# Pink-Noise-Filter.net
KiCad netlist of a schematic drawn in EAGLE
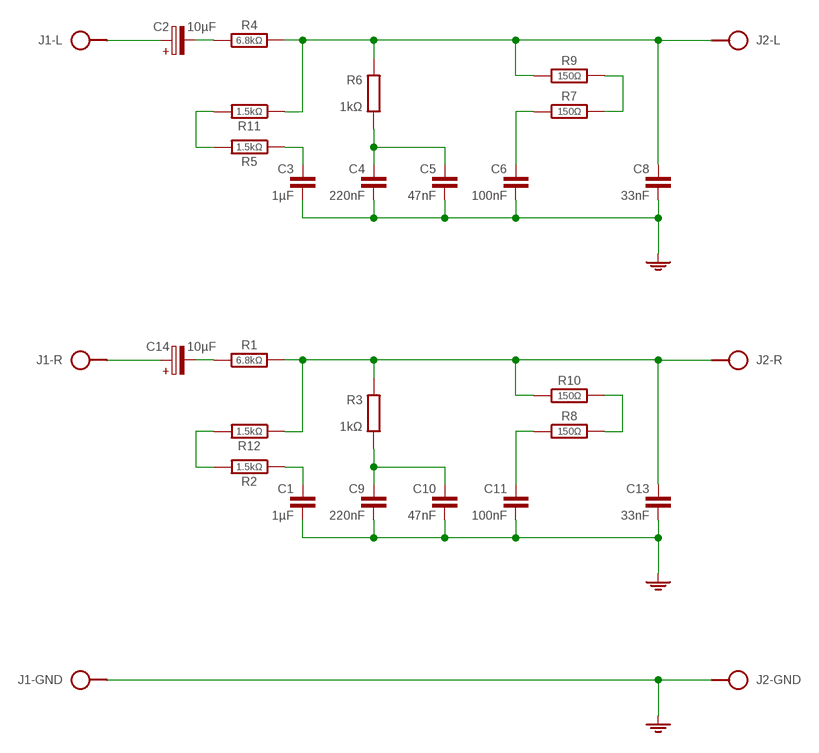
[diagram p0: schematic, sheet 1]

(export (version "E")
  (design (tool "Eeschema 10.0.6"))
  (components
    (comp (ref "C1")
      (value "1µF")
      (footprint "eagle-import:C050-045X075_V")
      (libsource (lib "eagle-import") (part "C050-045X075/V"))
    )
    (comp (ref "C2")
      (value "10µF")
      (footprint "eagle-import:E2,5-5")
      (libsource (lib "eagle-import") (part "CPOL-HE2,5-5"))
    )
    (comp (ref "C3")
      (value "1µF")
      (footprint "eagle-import:C050-045X075_V")
      (libsource (lib "eagle-import") (part "C050-045X075/V"))
    )
    (comp (ref "C4")
      (value "220nF")
      (footprint "eagle-import:C050-024X044_V")
      (libsource (lib "eagle-import") (part "C050-024X044/V"))
    )
    (comp (ref "C5")
      (value "47nF")
      (footprint "eagle-import:C050-020X044_V")
      (libsource (lib "eagle-import") (part "C050-020X044/V"))
    )
    (comp (ref "C6")
      (value "100nF")
      (footprint "eagle-import:C050-020X044_V")
      (libsource (lib "eagle-import") (part "C050-020X044/V"))
    )
    (comp (ref "C8")
      (value "33nF")
      (footprint "eagle-import:C050-020X044_V")
      (libsource (lib "eagle-import") (part "C050-020X044/V"))
    )
    (comp (ref "C9")
      (value "220nF")
      (footprint "eagle-import:C050-024X044_V")
      (libsource (lib "eagle-import") (part "C050-024X044/V"))
    )
    (comp (ref "C10")
      (value "47nF")
      (footprint "eagle-import:C050-020X044_V")
      (libsource (lib "eagle-import") (part "C050-020X044/V"))
    )
    (comp (ref "C11")
      (value "100nF")
      (footprint "eagle-import:C050-020X044_V")
      (libsource (lib "eagle-import") (part "C050-020X044/V"))
    )
    (comp (ref "C13")
      (value "33nF")
      (footprint "eagle-import:C050-020X044_V")
      (libsource (lib "eagle-import") (part "C050-020X044/V"))
    )
    (comp (ref "C14")
      (value "10µF")
      (footprint "eagle-import:E2,5-5")
      (libsource (lib "eagle-import") (part "CPOL-HE2,5-5"))
    )
    (comp (ref "J1")
      (value "SAUDIOL-GND-R")
      (footprint "eagle-import:SPAD-L-GND-R")
      (libsource (lib "eagle-import") (part "SAUDIOL-GND-R"))
    )
    (comp (ref "J2")
      (value "SAUDIOL-GND-R")
      (footprint "eagle-import:SPAD-L-GND-R")
      (libsource (lib "eagle-import") (part "SAUDIOL-GND-R"))
    )
    (comp (ref "R1")
      (value "6.8kΩ")
      (footprint "eagle-import:0204_10")
      (libsource (lib "eagle-import") (part "R-H0204/10"))
    )
    (comp (ref "R2")
      (value "1.5kΩ")
      (footprint "eagle-import:0204_10")
      (libsource (lib "eagle-import") (part "R-H0204/10"))
    )
    (comp (ref "R3")
      (value "1kΩ")
      (footprint "eagle-import:0204_10-V")
      (libsource (lib "eagle-import") (part "R0204/10-V"))
    )
    (comp (ref "R4")
      (value "6.8kΩ")
      (footprint "eagle-import:0204_10")
      (libsource (lib "eagle-import") (part "R-H0204/10"))
    )
    (comp (ref "R5")
      (value "1.5kΩ")
      (footprint "eagle-import:0204_10")
      (libsource (lib "eagle-import") (part "R-H0204/10"))
    )
    (comp (ref "R6")
      (value "1kΩ")
      (footprint "eagle-import:0204_10-V")
      (libsource (lib "eagle-import") (part "R0204/10-V"))
    )
    (comp (ref "R7")
      (value "150Ω")
      (footprint "eagle-import:0204_10")
      (libsource (lib "eagle-import") (part "R-H0204/10"))
    )
    (comp (ref "R8")
      (value "150Ω")
      (footprint "eagle-import:0204_10")
      (libsource (lib "eagle-import") (part "R-H0204/10"))
    )
    (comp (ref "R9")
      (value "150Ω")
      (footprint "eagle-import:0204_10")
      (libsource (lib "eagle-import") (part "R-H0204/10"))
    )
    (comp (ref "R10")
      (value "150Ω")
      (footprint "eagle-import:0204_10")
      (libsource (lib "eagle-import") (part "R-H0204/10"))
    )
    (comp (ref "R11")
      (value "1.5kΩ")
      (footprint "eagle-import:0204_10")
      (libsource (lib "eagle-import") (part "R-H0204/10"))
    )
    (comp (ref "R12")
      (value "1.5kΩ")
      (footprint "eagle-import:0204_10")
      (libsource (lib "eagle-import") (part "R-H0204/10"))
    )
  )
  (nets
    (net (code "1") (name "GND") (class "Default")
      (node (ref "C1") (pin "2") (pinfunction "2_2") (pintype "passive"))
      (node (ref "C10") (pin "2") (pinfunction "2_2") (pintype "passive"))
      (node (ref "C11") (pin "2") (pinfunction "2_2") (pintype "passive"))
      (node (ref "C13") (pin "2") (pinfunction "2_2") (pintype "passive"))
      (node (ref "C3") (pin "2") (pinfunction "2_2") (pintype "passive"))
      (node (ref "C4") (pin "2") (pinfunction "2_2") (pintype "passive"))
      (node (ref "C5") (pin "2") (pinfunction "2_2") (pintype "passive"))
      (node (ref "C6") (pin "2") (pinfunction "2_2") (pintype "passive"))
      (node (ref "C8") (pin "2") (pinfunction "2_2") (pintype "passive"))
      (node (ref "C9") (pin "2") (pinfunction "2_2") (pintype "passive"))
      (node (ref "J1") (pin "0") (pinfunction "P$1_0") (pintype "passive"))
      (node (ref "J2") (pin "0") (pinfunction "P$1_0") (pintype "passive"))
    )
    (net (code "2") (name "Net-(C1-Pad1)") (class "Default")
      (node (ref "C1") (pin "1") (pinfunction "1_1") (pintype "passive"))
      (node (ref "R2") (pin "1") (pinfunction "1_1") (pintype "passive"))
    )
    (net (code "3") (name "Net-(C2-Pad-)") (class "Default")
      (node (ref "C2") (pin "-") (pinfunction "-_-") (pintype "passive"))
      (node (ref "R4") (pin "1") (pinfunction "1_1") (pintype "passive"))
    )
    (net (code "4") (name "Net-(C3-Pad1)") (class "Default")
      (node (ref "C3") (pin "1") (pinfunction "1_1") (pintype "passive"))
      (node (ref "R5") (pin "1") (pinfunction "1_1") (pintype "passive"))
    )
    (net (code "5") (name "Net-(C6-Pad1)") (class "Default")
      (node (ref "C6") (pin "1") (pinfunction "1_1") (pintype "passive"))
      (node (ref "R7") (pin "1") (pinfunction "1_1") (pintype "passive"))
    )
    (net (code "6") (name "Net-(C11-Pad1)") (class "Default")
      (node (ref "C11") (pin "1") (pinfunction "1_1") (pintype "passive"))
      (node (ref "R8") (pin "1") (pinfunction "1_1") (pintype "passive"))
    )
    (net (code "7") (name "Net-(C14-Pad-)") (class "Default")
      (node (ref "C14") (pin "-") (pinfunction "-_-") (pintype "passive"))
      (node (ref "R1") (pin "1") (pinfunction "1_1") (pintype "passive"))
    )
    (net (code "8") (name "Net-(J1B-P$1)") (class "Default")
      (node (ref "C2") (pin "+") (pinfunction "+_+") (pintype "passive"))
      (node (ref "J1") (pin "L") (pinfunction "P$1_L") (pintype "passive"))
    )
    (net (code "9") (name "Net-(J1C-P$1)") (class "Default")
      (node (ref "C14") (pin "+") (pinfunction "+_+") (pintype "passive"))
      (node (ref "J1") (pin "R") (pinfunction "P$1_R") (pintype "passive"))
    )
    (net (code "10") (name "Net-(J2B-P$1)") (class "Default")
      (node (ref "C8") (pin "1") (pinfunction "1_1") (pintype "passive"))
      (node (ref "J2") (pin "L") (pinfunction "P$1_L") (pintype "passive"))
      (node (ref "R11") (pin "1") (pinfunction "1_1") (pintype "passive"))
      (node (ref "R4") (pin "2") (pinfunction "2_2") (pintype "passive"))
      (node (ref "R6") (pin "1") (pinfunction "2_1") (pintype "passive"))
      (node (ref "R9") (pin "1") (pinfunction "1_1") (pintype "passive"))
    )
    (net (code "11") (name "Net-(J2C-P$1)") (class "Default")
      (node (ref "C13") (pin "1") (pinfunction "1_1") (pintype "passive"))
      (node (ref "J2") (pin "R") (pinfunction "P$1_R") (pintype "passive"))
      (node (ref "R1") (pin "2") (pinfunction "2_2") (pintype "passive"))
      (node (ref "R10") (pin "1") (pinfunction "1_1") (pintype "passive"))
      (node (ref "R12") (pin "1") (pinfunction "1_1") (pintype "passive"))
      (node (ref "R3") (pin "1") (pinfunction "2_1") (pintype "passive"))
    )
    (net (code "12") (name "Net-(R3-1)") (class "Default")
      (node (ref "C10") (pin "1") (pinfunction "1_1") (pintype "passive"))
      (node (ref "C9") (pin "1") (pinfunction "1_1") (pintype "passive"))
      (node (ref "R3") (pin "2") (pinfunction "1_2") (pintype "passive"))
    )
    (net (code "13") (name "Net-(R6-1)") (class "Default")
      (node (ref "C4") (pin "1") (pinfunction "1_1") (pintype "passive"))
      (node (ref "C5") (pin "1") (pinfunction "1_1") (pintype "passive"))
      (node (ref "R6") (pin "2") (pinfunction "1_2") (pintype "passive"))
    )
    (net (code "14") (name "Net-(R7-Pad2)") (class "Default")
      (node (ref "R7") (pin "2") (pinfunction "2_2") (pintype "passive"))
      (node (ref "R9") (pin "2") (pinfunction "2_2") (pintype "passive"))
    )
    (net (code "15") (name "Net-(R10-Pad2)") (class "Default")
      (node (ref "R10") (pin "2") (pinfunction "2_2") (pintype "passive"))
      (node (ref "R8") (pin "2") (pinfunction "2_2") (pintype "passive"))
    )
    (net (code "16") (name "Net-(R11-Pad2)") (class "Default")
      (node (ref "R11") (pin "2") (pinfunction "2_2") (pintype "passive"))
      (node (ref "R5") (pin "2") (pinfunction "2_2") (pintype "passive"))
    )
    (net (code "17") (name "Net-(R12-Pad2)") (class "Default")
      (node (ref "R12") (pin "2") (pinfunction "2_2") (pintype "passive"))
      (node (ref "R2") (pin "2") (pinfunction "2_2") (pintype "passive"))
    )
  )
)
